# Rectifier.net
KiCad netlist of a schematic drawn in Altium Designer
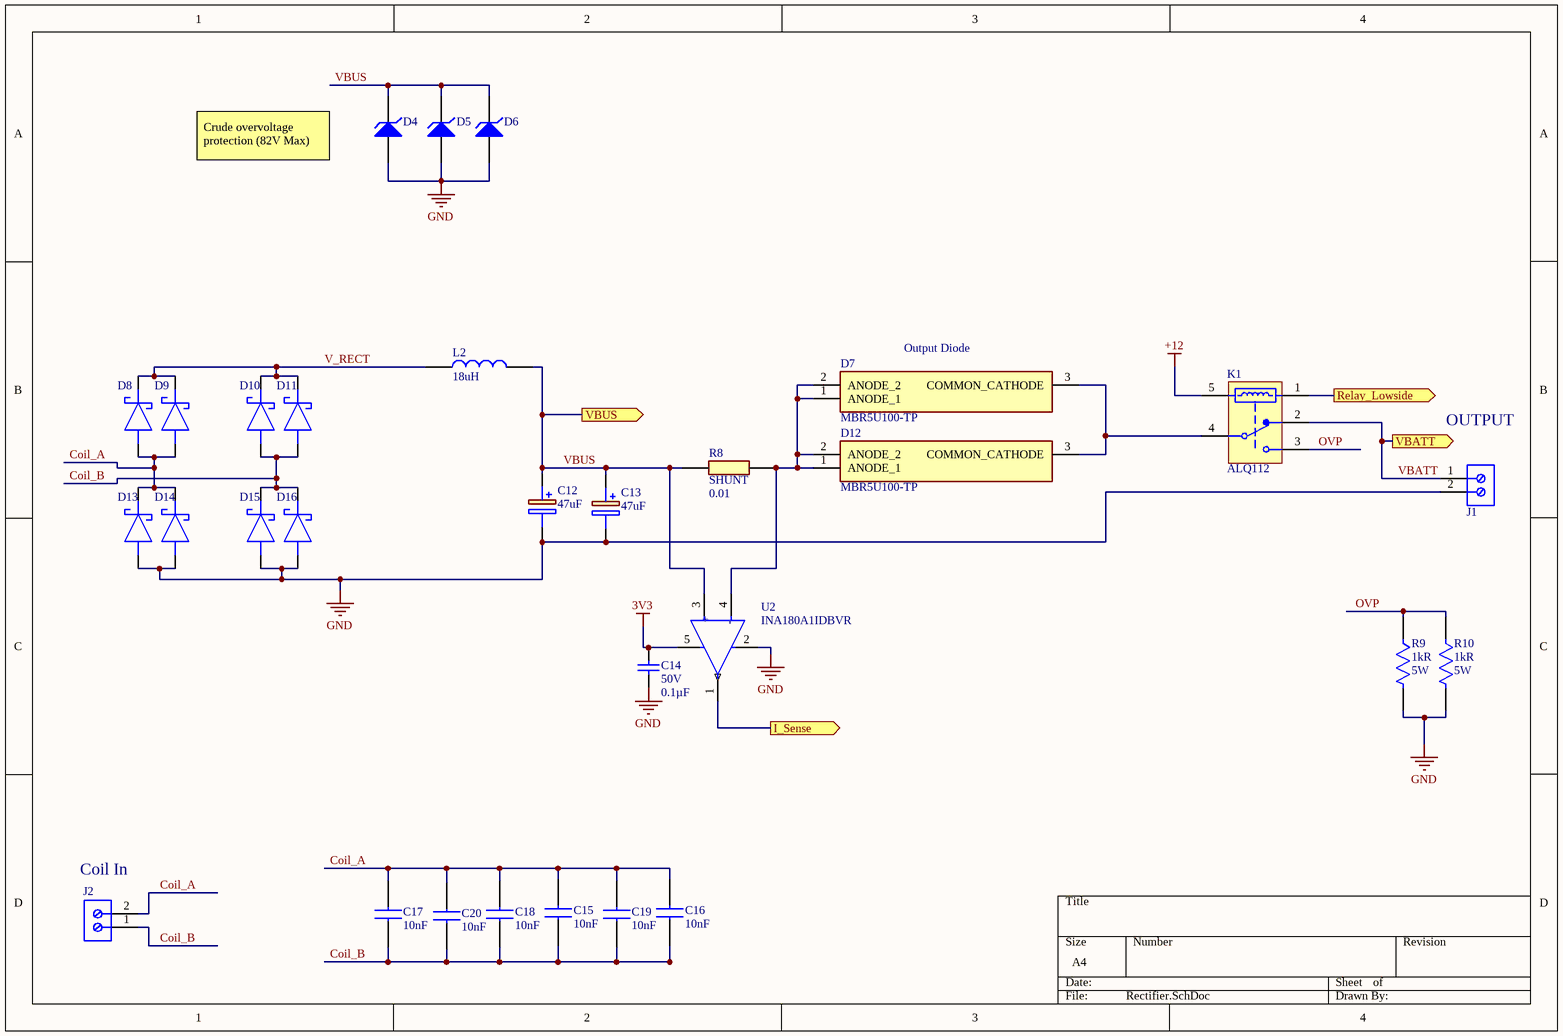
[diagram p0: Rectifier.SchDoc]

(export (version "E")
  (design (tool "Eeschema 10.0.6"))
  (components
    (comp (ref "C12")
      (value "UCD1K470MNL1GS")
      (footprint "SamacSys:CAPAE1030X1080N")
      (description "Capacitor Polarised")
      (fields (field (name "MOUSER PART NUMBER") "647-UCD1K470MNL1GS") (field (name "CAPACITANCE") "47uF"))
      (libsource (lib "*") (part "UCD1K470MNL1GS"))
    )
    (comp (ref "C13")
      (value "UCD1K470MNL1GS")
      (footprint "SamacSys:CAPAE1030X1080N")
      (description "Capacitor Polarised")
      (fields (field (name "MOUSER PART NUMBER") "647-UCD1K470MNL1GS") (field (name "CAPACITANCE") "47uF"))
      (libsource (lib "*") (part "UCD1K470MNL1GS"))
    )
    (comp (ref "C14")
      (value "C0805C104K5RACTU")
      (footprint "CAP0805")
      (description "CAP CER 0.1UF 50V X7R 0805")
      (fields
        (field (name "TOLERANCE") "±10%")
        (field (name "VOLTAGE - RATED") "50V")
        (field (name "CAPACITANCE") "0.1µF")
      )
      (libsource (lib "Capacitors") (part "C0805C104K5RACTU"))
    )
    (comp (ref "C15")
      (value "C1206C103JAGECAUTO")
      (footprint "SamacSys:CAPC3216X110N")
      (description "Capacitor")
      (fields (field (name "MOUSER PART NUMBER") "80-C1206C103JAGECAUT") (field (name "CAPACITANCE") "10nF"))
      (libsource (lib "*") (part "C1206C103JAGECAUTO"))
    )
    (comp (ref "C16")
      (value "C1206C103JAGECAUTO")
      (footprint "SamacSys:CAPC3216X110N")
      (description "Capacitor")
      (fields (field (name "MOUSER PART NUMBER") "80-C1206C103JAGECAUT") (field (name "CAPACITANCE") "10nF"))
      (libsource (lib "*") (part "C1206C103JAGECAUTO"))
    )
    (comp (ref "C17")
      (value "C1206C103JAGECAUTO")
      (footprint "SamacSys:CAPC3216X110N")
      (description "Capacitor")
      (fields (field (name "MOUSER PART NUMBER") "80-C1206C103JAGECAUT") (field (name "CAPACITANCE") "10nF"))
      (libsource (lib "*") (part "C1206C103JAGECAUTO"))
    )
    (comp (ref "C18")
      (value "C1206C103JAGECAUTO")
      (footprint "SamacSys:CAPC3216X110N")
      (description "Capacitor")
      (fields (field (name "MOUSER PART NUMBER") "80-C1206C103JAGECAUT") (field (name "CAPACITANCE") "10nF"))
      (libsource (lib "*") (part "C1206C103JAGECAUTO"))
    )
    (comp (ref "C19")
      (value "C1206C103JAGECAUTO")
      (footprint "SamacSys:CAPC3216X110N")
      (description "Capacitor")
      (fields (field (name "MOUSER PART NUMBER") "80-C1206C103JAGECAUT") (field (name "CAPACITANCE") "10nF"))
      (libsource (lib "*") (part "C1206C103JAGECAUTO"))
    )
    (comp (ref "C20")
      (value "C1206C103JAGECAUTO")
      (footprint "SamacSys:CAPC3216X110N")
      (description "Capacitor")
      (fields (field (name "MOUSER PART NUMBER") "80-C1206C103JAGECAUT") (field (name "CAPACITANCE") "10nF"))
      (libsource (lib "*") (part "C1206C103JAGECAUTO"))
    )
    (comp (ref "D4")
      (value "1SMB5947BT3G")
      (footprint "ONSC-SMB-2-403A-03_H_V")
      (description "3 W Zener Voltage Regulator, 2-Pin SMB, Pb-Free, Tape and Reel")
      (fields (field (name "MANUFACTURER") "On Semiconductor"))
      (libsource (lib "Altium Content Vault") (part "ONSC-K1A2-2"))
    )
    (comp (ref "D5")
      (value "1SMB5947BT3G")
      (footprint "ONSC-SMB-2-403A-03_H_V")
      (description "3 W Zener Voltage Regulator, 2-Pin SMB, Pb-Free, Tape and Reel")
      (fields (field (name "MANUFACTURER") "On Semiconductor"))
      (libsource (lib "Altium Content Vault") (part "ONSC-K1A2-2"))
    )
    (comp (ref "D6")
      (value "1SMB5947BT3G")
      (footprint "ONSC-SMB-2-403A-03_H_V")
      (description "3 W Zener Voltage Regulator, 2-Pin SMB, Pb-Free, Tape and Reel")
      (fields (field (name "MANUFACTURER") "On Semiconductor"))
      (libsource (lib "Altium Content Vault") (part "ONSC-K1A2-2"))
    )
    (comp (ref "D7")
      (value "MBR5U100-TP")
      (footprint "WPT_Receiver_lib:MBR5U100TP")
      (description "Schottky Diode")
      (libsource (lib "WPT_Receiver_lib") (part "MBR5U100-TP"))
    )
    (comp (ref "D8")
      (value "STPS4S200UFN")
      (footprint "SamacSys:SODFL5436X110N")
      (description "Schottky Diode")
      (fields (field (name "MOUSER PART NUMBER") "511-STPS4S200UFN"))
      (libsource (lib "*") (part "STPS4S200UFN"))
    )
    (comp (ref "D9")
      (value "STPS4S200UFN")
      (footprint "SamacSys:SODFL5436X110N")
      (description "Schottky Diode")
      (fields (field (name "MOUSER PART NUMBER") "511-STPS4S200UFN"))
      (libsource (lib "*") (part "STPS4S200UFN"))
    )
    (comp (ref "D10")
      (value "STPS4S200UFN")
      (footprint "SamacSys:SODFL5436X110N")
      (description "Schottky Diode")
      (fields (field (name "MOUSER PART NUMBER") "511-STPS4S200UFN"))
      (libsource (lib "*") (part "STPS4S200UFN"))
    )
    (comp (ref "D11")
      (value "STPS4S200UFN")
      (footprint "SamacSys:SODFL5436X110N")
      (description "Schottky Diode")
      (fields (field (name "MOUSER PART NUMBER") "511-STPS4S200UFN"))
      (libsource (lib "*") (part "STPS4S200UFN"))
    )
    (comp (ref "D12")
      (value "MBR5U100-TP")
      (footprint "WPT_Receiver_lib:MBR5U100TP")
      (description "Schottky Diode")
      (libsource (lib "WPT_Receiver_lib") (part "MBR5U100-TP"))
    )
    (comp (ref "D13")
      (value "STPS4S200UFN")
      (footprint "SamacSys:SODFL5436X110N")
      (description "Schottky Diode")
      (fields (field (name "MOUSER PART NUMBER") "511-STPS4S200UFN"))
      (libsource (lib "*") (part "STPS4S200UFN"))
    )
    (comp (ref "D14")
      (value "STPS4S200UFN")
      (footprint "SamacSys:SODFL5436X110N")
      (description "Schottky Diode")
      (fields (field (name "MOUSER PART NUMBER") "511-STPS4S200UFN"))
      (libsource (lib "*") (part "STPS4S200UFN"))
    )
    (comp (ref "D15")
      (value "STPS4S200UFN")
      (footprint "SamacSys:SODFL5436X110N")
      (description "Schottky Diode")
      (fields (field (name "MOUSER PART NUMBER") "511-STPS4S200UFN"))
      (libsource (lib "*") (part "STPS4S200UFN"))
    )
    (comp (ref "D16")
      (value "STPS4S200UFN")
      (footprint "SamacSys:SODFL5436X110N")
      (description "Schottky Diode")
      (fields (field (name "MOUSER PART NUMBER") "511-STPS4S200UFN"))
      (libsource (lib "*") (part "STPS4S200UFN"))
    )
    (comp (ref "J1")
      (value "691137710002")
      (footprint "691137710002")
      (description "Series 1377 - 5.00 mm Horizontal Entry with Pressure Clamp WR-TBL, 2 pin")
      (fields (field (name "MANUFACTURER") "Wurth Elektronik") (field (name "PUBLISHER") "WurthElektronik"))
      (libsource (lib "Altium Content Vault") (part "WE-CN-1P-F-TB2"))
    )
    (comp (ref "J2")
      (value "691137710002")
      (footprint "691137710002")
      (description "Series 1377 - 5.00 mm Horizontal Entry with Pressure Clamp WR-TBL, 2 pin")
      (fields (field (name "MANUFACTURER") "Wurth Elektronik") (field (name "PUBLISHER") "WurthElektronik"))
      (libsource (lib "Altium Content Vault") (part "WE-CN-1P-F-TB2"))
    )
    (comp (ref "K1")
      (value "ALQ112")
      (footprint "PNSC-LQ-5-2000x1000x1600_V")
      (fields (field (name "MANUFACTURER") "Panasonic"))
      (libsource (lib "Altium Content Vault") (part "PNSC-ALQ112-LQ-5-2000x1000x1600-5"))
    )
    (comp (ref "L2")
      (value "SDR1307-180ML")
      (footprint "SamacSys:SDR1307-220ML")
      (description "Inductor")
      (fields (field (name "MOUSER PART NUMBER") "652-SDR1307-180ML") (field (name "INDUCTANCE") "18uH"))
      (libsource (lib "*") (part "SDR1307-180ML"))
    )
    (comp (ref "R8")
      (value "SHUNT")
      (footprint "SamacSys:RESC6434X90N")
      (description "Resistor")
      (fields
        (field (name "MANUFACTURER_PART_NUMBER") "CRA2512-FZ-R010ELF")
        (field (name "MOUSER PART NUMBER") "652-CRA2512FZR010ELF")
        (field (name "RESISTANCE") "0.01")
      )
      (libsource (lib "*") (part "CRA2512-FZ-R010ELF"))
    )
    (comp (ref "R9")
      (value "SMF51K0JT")
      (footprint "FP-SMF5-MFG")
      (description "RES SMD 1K OHM 5% 5W 5329")
      (fields
        (field (name "RESISTANCE") "1kR")
        (field (name "TOLERANCE") "5%")
        (field (name "MAX POWER DISSIPATION") "5W")
      )
      (libsource (lib "Altium Content Vault") (part "1029c3af85768c4190bb7ad29bc67b5"))
    )
    (comp (ref "R10")
      (value "SMF51K0JT")
      (footprint "FP-SMF5-MFG")
      (description "RES SMD 1K OHM 5% 5W 5329")
      (fields
        (field (name "RESISTANCE") "1kR")
        (field (name "TOLERANCE") "5%")
        (field (name "MAX POWER DISSIPATION") "5W")
      )
      (libsource (lib "Altium Content Vault") (part "1029c3af85768c4190bb7ad29bc67b5"))
    )
    (comp (ref "U2")
      (value "INA180A1IDBVR")
      (footprint "FP-DBV0005A-IPC_A")
      (description "IC CURR SENSE 1 CIRCUIT SOT23-5")
      (libsource (lib "Altium Content Vault") (part "0a55cf1a948ad01a3239aec1b7efad0"))
    )
  )
  (nets
    (net (code "1") (name "+12") (class "Default")
      (node (ref "K1") (pin "5") (pinfunction "5_5") (pintype "passive"))
    )
    (net (code "2") (name "/Coil_A") (class "Default")
      (node (ref "C15") (pin "1") (pinfunction "1_1") (pintype "passive"))
      (node (ref "C16") (pin "1") (pinfunction "1_1") (pintype "passive"))
      (node (ref "C17") (pin "1") (pinfunction "1_1") (pintype "passive"))
      (node (ref "C18") (pin "1") (pinfunction "1_1") (pintype "passive"))
      (node (ref "C19") (pin "1") (pinfunction "1_1") (pintype "passive"))
      (node (ref "C20") (pin "1") (pinfunction "1_1") (pintype "passive"))
      (node (ref "D13") (pin "1") (pinfunction "K_1") (pintype "passive"))
      (node (ref "D14") (pin "1") (pinfunction "K_1") (pintype "passive"))
      (node (ref "D8") (pin "2") (pinfunction "A_2") (pintype "passive"))
      (node (ref "D9") (pin "2") (pinfunction "A_2") (pintype "passive"))
      (node (ref "J2") (pin "2") (pinfunction "2_2") (pintype "passive"))
    )
    (net (code "3") (name "/Coil_B") (class "Default")
      (node (ref "C15") (pin "2") (pinfunction "2_2") (pintype "passive"))
      (node (ref "C16") (pin "2") (pinfunction "2_2") (pintype "passive"))
      (node (ref "C17") (pin "2") (pinfunction "2_2") (pintype "passive"))
      (node (ref "C18") (pin "2") (pinfunction "2_2") (pintype "passive"))
      (node (ref "C19") (pin "2") (pinfunction "2_2") (pintype "passive"))
      (node (ref "C20") (pin "2") (pinfunction "2_2") (pintype "passive"))
      (node (ref "D10") (pin "2") (pinfunction "A_2") (pintype "passive"))
      (node (ref "D11") (pin "2") (pinfunction "A_2") (pintype "passive"))
      (node (ref "D15") (pin "1") (pinfunction "K_1") (pintype "passive"))
      (node (ref "D16") (pin "1") (pinfunction "K_1") (pintype "passive"))
      (node (ref "J2") (pin "1") (pinfunction "1_1") (pintype "passive"))
    )
    (net (code "4") (name "/I_Sense") (class "Default")
      (node (ref "U2") (pin "1") (pinfunction "OUT_1") (pintype "output"))
    )
    (net (code "5") (name "/OVP") (class "Default")
      (node (ref "K1") (pin "3") (pinfunction "NO_3") (pintype "passive"))
      (node (ref "R10") (pin "1") (pinfunction "1_1") (pintype "passive"))
      (node (ref "R9") (pin "1") (pinfunction "1_1") (pintype "passive"))
    )
    (net (code "6") (name "/Relay_Lowside") (class "Default")
      (node (ref "K1") (pin "1") (pinfunction "1_1") (pintype "passive"))
    )
    (net (code "7") (name "/VBATT") (class "Default")
      (node (ref "J1") (pin "1") (pinfunction "1_1") (pintype "passive"))
      (node (ref "K1") (pin "2") (pinfunction "NC_2") (pintype "passive"))
    )
    (net (code "8") (name "/VBUS") (class "Default")
      (node (ref "C12") (pin "1") (pinfunction "+_1") (pintype "passive"))
      (node (ref "C13") (pin "1") (pinfunction "+_1") (pintype "passive"))
      (node (ref "D4") (pin "1") (pinfunction "K_1") (pintype "passive"))
      (node (ref "D5") (pin "1") (pinfunction "K_1") (pintype "passive"))
      (node (ref "D6") (pin "1") (pinfunction "K_1") (pintype "passive"))
      (node (ref "L2") (pin "2") (pinfunction "2_2") (pintype "passive"))
      (node (ref "R8") (pin "1") (pinfunction "1_1") (pintype "passive"))
      (node (ref "U2") (pin "3") (pinfunction "IN+_3") (pintype "tri_state"))
    )
    (net (code "9") (name "/V_RECT") (class "Default")
      (node (ref "D10") (pin "1") (pinfunction "K_1") (pintype "passive"))
      (node (ref "D11") (pin "1") (pinfunction "K_1") (pintype "passive"))
      (node (ref "D8") (pin "1") (pinfunction "K_1") (pintype "passive"))
      (node (ref "D9") (pin "1") (pinfunction "K_1") (pintype "passive"))
      (node (ref "L2") (pin "1") (pinfunction "1_1") (pintype "passive"))
    )
    (net (code "10") (name "3V3") (class "Default")
      (node (ref "C14") (pin "2") (pinfunction "2_2") (pintype "passive"))
      (node (ref "U2") (pin "5") (pinfunction "VS_5") (pintype "power_in"))
    )
    (net (code "11") (name "GND") (class "Default")
      (node (ref "C12") (pin "2") (pinfunction "-_2") (pintype "passive"))
      (node (ref "C13") (pin "2") (pinfunction "-_2") (pintype "passive"))
      (node (ref "C14") (pin "1") (pinfunction "1_1") (pintype "passive"))
      (node (ref "D13") (pin "2") (pinfunction "A_2") (pintype "passive"))
      (node (ref "D14") (pin "2") (pinfunction "A_2") (pintype "passive"))
      (node (ref "D15") (pin "2") (pinfunction "A_2") (pintype "passive"))
      (node (ref "D16") (pin "2") (pinfunction "A_2") (pintype "passive"))
      (node (ref "D4") (pin "2") (pinfunction "A_2") (pintype "passive"))
      (node (ref "D5") (pin "2") (pinfunction "A_2") (pintype "passive"))
      (node (ref "D6") (pin "2") (pinfunction "A_2") (pintype "passive"))
      (node (ref "J1") (pin "2") (pinfunction "2_2") (pintype "passive"))
      (node (ref "R10") (pin "2") (pinfunction "2_2") (pintype "passive"))
      (node (ref "R9") (pin "2") (pinfunction "2_2") (pintype "passive"))
      (node (ref "U2") (pin "2") (pinfunction "GND_2") (pintype "power_in"))
    )
    (net (code "12") (name "Net-(D12-ANODE_1)") (class "Default")
      (node (ref "D12") (pin "1") (pinfunction "ANODE_1_1") (pintype "passive"))
      (node (ref "D12") (pin "2") (pinfunction "ANODE_2_2") (pintype "passive"))
      (node (ref "D7") (pin "1") (pinfunction "ANODE_1_1") (pintype "passive"))
      (node (ref "D7") (pin "2") (pinfunction "ANODE_2_2") (pintype "passive"))
      (node (ref "R8") (pin "2") (pinfunction "2_2") (pintype "passive"))
      (node (ref "U2") (pin "4") (pinfunction "IN-_4") (pintype "tri_state"))
    )
    (net (code "13") (name "Net-(D12-COMMON_CATHODE)") (class "Default")
      (node (ref "D12") (pin "3") (pinfunction "COMMON_CATHODE_3") (pintype "passive"))
      (node (ref "D7") (pin "3") (pinfunction "COMMON_CATHODE_3") (pintype "passive"))
      (node (ref "K1") (pin "4") (pinfunction "COM_4") (pintype "passive"))
    )
  )
)
